# Sheet1.net
KiCad netlist of a schematic drawn in Altium Designer
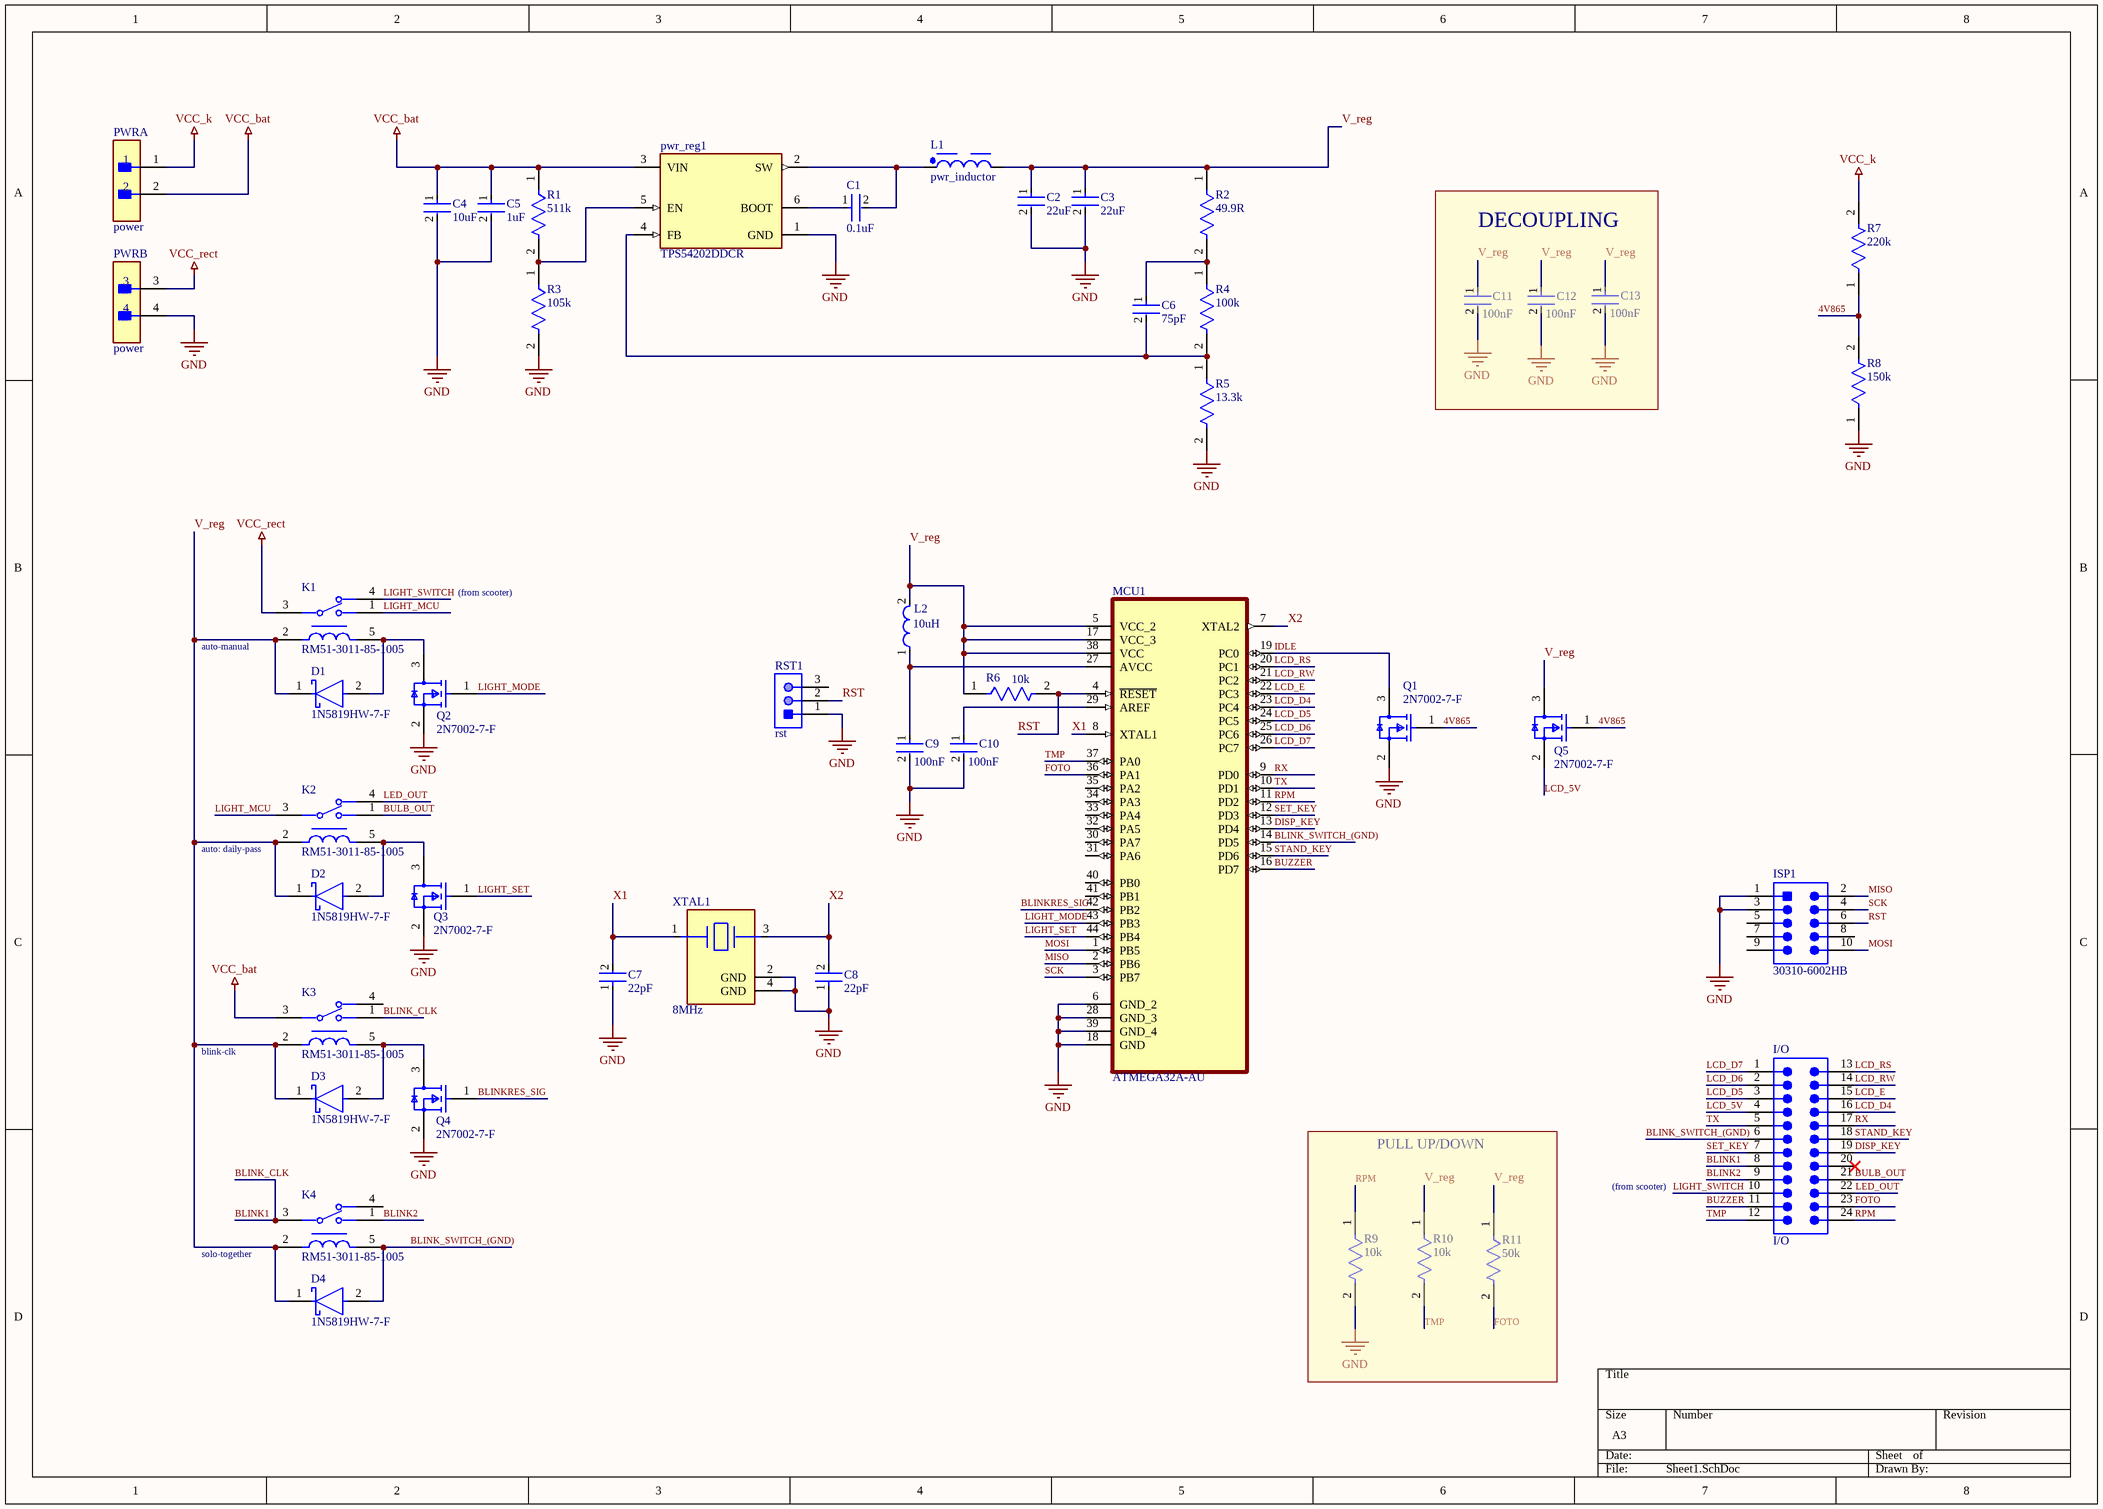
[diagram p0: Sheet1.SchDoc]

(export (version "E")
  (design (tool "Eeschema 10.0.6"))
  (components
    (comp (ref "C1")
      (value "0.1uF")
      (footprint "FP-CL10-IPC_A")
      (description "Cap Ceramic 0.1uF 25V SMD 0603")
      (fields (field (name "VOLTAGE") "50V") (field (name "TOLERANCE") "10%"))
      (libsource (lib "Altium Content Vault") (part "b4654b650e69147ec39a6b967a45e02"))
    )
    (comp (ref "C2")
      (value "22uF")
      (footprint "FP-CL10-IPC_A")
      (description "Cap Ceramic 22uF 25V X7R LOW ESR SMD 0603")
      (fields (field (name "VOLTAGE") "50V") (field (name "TOLERANCE") "10%"))
      (libsource (lib "Altium Content Vault") (part "b4654b650e69147ec39a6b967a45e02"))
    )
    (comp (ref "C3")
      (value "22uF")
      (footprint "FP-CL10-IPC_A")
      (description "Cap Ceramic 22uF 25V X7R LOW ESR SMD 0603")
      (fields (field (name "VOLTAGE") "50V") (field (name "TOLERANCE") "10%"))
      (libsource (lib "Altium Content Vault") (part "b4654b650e69147ec39a6b967a45e02"))
    )
    (comp (ref "C4")
      (value "10uF")
      (footprint "FP-CL10-IPC_A")
      (description "Cap Ceramic 10uF 25V SMD 0603")
      (fields (field (name "VOLTAGE") "50V") (field (name "TOLERANCE") "10%"))
      (libsource (lib "Altium Content Vault") (part "b4654b650e69147ec39a6b967a45e02"))
    )
    (comp (ref "C5")
      (value "1uF")
      (footprint "FP-CL10-IPC_A")
      (description "Cap Ceramic 1uF 25V SMD 0603")
      (fields (field (name "VOLTAGE") "50V") (field (name "TOLERANCE") "10%"))
      (libsource (lib "Altium Content Vault") (part "b4654b650e69147ec39a6b967a45e02"))
    )
    (comp (ref "C6")
      (value "75pF")
      (footprint "FP-CL10-IPC_A")
      (description "Cap Ceramic 75pF 25V SMD 0603")
      (fields (field (name "VOLTAGE") "50V") (field (name "TOLERANCE") "10%"))
      (libsource (lib "Altium Content Vault") (part "b4654b650e69147ec39a6b967a45e02"))
    )
    (comp (ref "C7")
      (value "22pF")
      (footprint "FP-CL10-IPC_A")
      (description "Cap Ceramic 22pF 25V SMD 0603")
      (fields (field (name "VOLTAGE") "50V") (field (name "TOLERANCE") "10%"))
      (libsource (lib "Altium Content Vault") (part "b4654b650e69147ec39a6b967a45e02"))
    )
    (comp (ref "C8")
      (value "22pF")
      (footprint "FP-CL10-IPC_A")
      (description "Cap Ceramic 22pF 25V SMD 0603")
      (fields (field (name "VOLTAGE") "50V") (field (name "TOLERANCE") "10%"))
      (libsource (lib "Altium Content Vault") (part "b4654b650e69147ec39a6b967a45e02"))
    )
    (comp (ref "C9")
      (value "100nF")
      (footprint "FP-CL10-IPC_A")
      (description "Cap Ceramic 100nF 50V X7R ±10% Pad SMD 0603 +125°C T/R")
      (fields (field (name "VOLTAGE") "50V") (field (name "TOLERANCE") "10%"))
      (libsource (lib "Altium Content Vault") (part "b4654b650e69147ec39a6b967a45e02"))
    )
    (comp (ref "C10")
      (value "100nF")
      (footprint "FP-CL10-IPC_A")
      (description "Cap Ceramic 100nF 50V X7R ±10% Pad SMD 0603 +125°C T/R")
      (fields (field (name "VOLTAGE") "50V") (field (name "TOLERANCE") "10%"))
      (libsource (lib "Altium Content Vault") (part "b4654b650e69147ec39a6b967a45e02"))
    )
    (comp (ref "C11")
      (value "100nF")
      (footprint "FP-CL10-IPC_A")
      (description "Cap Ceramic 100nF 50V X7R ±10% Pad SMD 0603 +125°C T/R")
      (fields (field (name "VOLTAGE") "50V") (field (name "TOLERANCE") "10%"))
      (libsource (lib "Altium Content Vault") (part "b4654b650e69147ec39a6b967a45e02"))
    )
    (comp (ref "C12")
      (value "100nF")
      (footprint "FP-CL10-IPC_A")
      (description "Cap Ceramic 100nF 50V X7R ±10% Pad SMD 0603 +125°C T/R")
      (fields (field (name "VOLTAGE") "50V") (field (name "TOLERANCE") "10%"))
      (libsource (lib "Altium Content Vault") (part "b4654b650e69147ec39a6b967a45e02"))
    )
    (comp (ref "C13")
      (value "100nF")
      (footprint "FP-CL10-IPC_A")
      (description "Cap Ceramic 100nF 50V X7R ±10% Pad SMD 0603 +125°C T/R")
      (fields (field (name "VOLTAGE") "50V") (field (name "TOLERANCE") "10%"))
      (libsource (lib "Altium Content Vault") (part "b4654b650e69147ec39a6b967a45e02"))
    )
    (comp (ref "D1")
      (value "1N5819HW-7-F")
      (footprint "FP-SOD123-IPC_A")
      (description "DIODE SCHOTTKY 40V 1A SOD123")
      (libsource (lib "Altium Content Vault") (part "1d6ec82d83fb6aee721767c19dac4b9"))
    )
    (comp (ref "D2")
      (value "1N5819HW-7-F")
      (footprint "FP-SOD123-IPC_A")
      (description "DIODE SCHOTTKY 40V 1A SOD123")
      (libsource (lib "Altium Content Vault") (part "1d6ec82d83fb6aee721767c19dac4b9"))
    )
    (comp (ref "D3")
      (value "1N5819HW-7-F")
      (footprint "FP-SOD123-IPC_A")
      (description "DIODE SCHOTTKY 40V 1A SOD123")
      (libsource (lib "Altium Content Vault") (part "1d6ec82d83fb6aee721767c19dac4b9"))
    )
    (comp (ref "D4")
      (value "1N5819HW-7-F")
      (footprint "FP-SOD123-IPC_A")
      (description "DIODE SCHOTTKY 40V 1A SOD123")
      (libsource (lib "Altium Content Vault") (part "1d6ec82d83fb6aee721767c19dac4b9"))
    )
    (comp (ref "I/O")
      (value "I/O")
      (footprint "649024227222")
      (libsource (lib "Altium Content Vault") (part "Header_Male_2R_24P(A)"))
    )
    (comp (ref "ISP1")
      (value "30310-6002HB")
      (footprint "3M-30310-6002HB-10_V")
      (fields (field (name "MANUFACTURER") "3M"))
      (libsource (lib "Altium Content Vault") (part "CN-2P-M-R10"))
    )
    (comp (ref "K1")
      (value "RM51-3011-85-1005")
      (footprint "FP-1-1721150-0-MFG")
      (description "Relpol\r\nRM51-3011-85-1005\r\nRELAY 10A 5V")
      (fields
        (field (name "MANUFACTURER") "TE")
        (field (name "OCTOPART") "https://octopart.com/1-1721150-0-te+connectivity-41294869")
      )
      (libsource (lib "Altium Content Vault") (part "6d7f6cec76f9d90da65a396cf24d809"))
    )
    (comp (ref "K2")
      (value "RM51-3011-85-1005")
      (footprint "FP-1-1721150-0-MFG")
      (description "Relpol\r\nRM51-3011-85-1005\r\nRELAY 10A 5V")
      (fields
        (field (name "MANUFACTURER") "TE")
        (field (name "OCTOPART") "https://octopart.com/1-1721150-0-te+connectivity-41294869")
      )
      (libsource (lib "Altium Content Vault") (part "6d7f6cec76f9d90da65a396cf24d809"))
    )
    (comp (ref "K3")
      (value "RM51-3011-85-1005")
      (footprint "FP-1-1721150-0-MFG")
      (description "Relpol\r\nRM51-3011-85-1005\r\nRELAY 10A 5V")
      (fields
        (field (name "MANUFACTURER") "TE")
        (field (name "OCTOPART") "https://octopart.com/1-1721150-0-te+connectivity-41294869")
      )
      (libsource (lib "Altium Content Vault") (part "6d7f6cec76f9d90da65a396cf24d809"))
    )
    (comp (ref "K4")
      (value "RM51-3011-85-1005")
      (footprint "FP-1-1721150-0-MFG")
      (description "Relpol\r\nRM51-3011-85-1005\r\nRELAY 10A 5V")
      (fields
        (field (name "MANUFACTURER") "TE")
        (field (name "OCTOPART") "https://octopart.com/1-1721150-0-te+connectivity-41294869")
      )
      (libsource (lib "Altium Content Vault") (part "6d7f6cec76f9d90da65a396cf24d809"))
    )
    (comp (ref "L1")
      (value "pwr_inductor")
      (footprint "WE-PD_7345")
      (description "15uF, 2.7A  HPI0630-150")
      (fields (field (name "TOLERANCE") "20%"))
      (libsource (lib "Altium Content Vault") (part "Inductor - 2"))
    )
    (comp (ref "L2")
      (value "10uH")
      (footprint "FP-CBMF1608-IPC_A")
      (description "SMD Inductors 10uH ±10% 0.38A 0.468Ω 0603")
      (fields (field (name "TOLERANCE") "10%"))
      (libsource (lib "Altium Content Vault") (part "725321dda6339637d4d059423bc1c3c"))
    )
    (comp (ref "MCU1")
      (value "ATMEGA32A-AU")
      (footprint "QFP80P1200X1200X120-44N")
      (description "AVR AVRÂ® ATmega Microcontroller IC 8-Bit 16MHz 32KB (16K x 16) FLASH 44-TQFP (10x10)")
      (fields (field (name "MF") "Microchip"))
      (libsource (lib "ATMEGA32A-AU") (part "ATMEGA32A-AU"))
    )
    (comp (ref "PWR")
      (value "power")
      (footprint "FP-1586042-4-MFG")
      (description "CONN HEADER R/A 4POS 4.2MM")
      (libsource (lib "Altium Content Vault") (part "54be066d535c0aa4221644b3767ed93"))
    )
    (comp (ref "pwr_reg1")
      (value "TPS54202DDCR")
      (footprint "FP-DDC0006A-IPC_B")
      (description "IC REG BUCK ADJ 2A TSOT23-6")
      (libsource (lib "Altium Content Vault") (part "35c2d3f1afc239a386b2ba50eead654"))
    )
    (comp (ref "Q1")
      (value "2N7002-7-F")
      (footprint "FP-SOT23-MFG")
      (description "MOSFET N-CH 60V 115MA SOT23-3")
      (fields (field (name "VOLTAGE") "60V"))
      (libsource (lib "Altium Content Vault") (part "3b9c635fedb024a5347a57b145af9cc"))
    )
    (comp (ref "Q2")
      (value "2N7002-7-F")
      (footprint "FP-SOT23-MFG")
      (description "MOSFET N-CH 60V 115MA SOT23-3")
      (fields (field (name "VOLTAGE") "60V"))
      (libsource (lib "Altium Content Vault") (part "3b9c635fedb024a5347a57b145af9cc"))
    )
    (comp (ref "Q3")
      (value "2N7002-7-F")
      (footprint "FP-SOT23-MFG")
      (description "MOSFET N-CH 60V 115MA SOT23-3")
      (fields (field (name "VOLTAGE") "60V"))
      (libsource (lib "Altium Content Vault") (part "3b9c635fedb024a5347a57b145af9cc"))
    )
    (comp (ref "Q4")
      (value "2N7002-7-F")
      (footprint "FP-SOT23-MFG")
      (description "MOSFET N-CH 60V 115MA SOT23-3")
      (fields (field (name "VOLTAGE") "60V"))
      (libsource (lib "Altium Content Vault") (part "3b9c635fedb024a5347a57b145af9cc"))
    )
    (comp (ref "Q5")
      (value "2N7002-7-F")
      (footprint "FP-SOT23-MFG")
      (description "MOSFET N-CH 60V 115MA SOT23-3")
      (fields (field (name "VOLTAGE") "60V"))
      (libsource (lib "Altium Content Vault") (part "3b9c635fedb024a5347a57b145af9cc"))
    )
    (comp (ref "R1")
      (value "511k")
      (footprint "FP-CRCW0603-e3-IPC_A")
      (description "511kΩ, 0.1W, 0603")
      (fields (field (name "TOLERANCE") "1%"))
      (libsource (lib "Altium Content Vault") (part "1029c3af85768c4190bb7ad29bc67b5"))
    )
    (comp (ref "R2")
      (value "49.9R")
      (footprint "FP-CRCW0603-e3-IPC_A")
      (description "49.9Ω, 0.1W, 0603")
      (fields (field (name "TOLERANCE") "1%"))
      (libsource (lib "Altium Content Vault") (part "1029c3af85768c4190bb7ad29bc67b5"))
    )
    (comp (ref "R3")
      (value "105k")
      (footprint "FP-CRCW0603-e3-IPC_A")
      (description "105kΩ, 0.1W, 0603")
      (fields (field (name "TOLERANCE") "1%"))
      (libsource (lib "Altium Content Vault") (part "1029c3af85768c4190bb7ad29bc67b5"))
    )
    (comp (ref "R4")
      (value "100k")
      (footprint "FP-CRCW0603-e3-IPC_A")
      (description "100kΩ, 0.1W, 0603")
      (fields (field (name "TOLERANCE") "1%"))
      (libsource (lib "Altium Content Vault") (part "1029c3af85768c4190bb7ad29bc67b5"))
    )
    (comp (ref "R5")
      (value "13.3k")
      (footprint "FP-CRCW0603-e3-IPC_A")
      (description "13.3kΩ, 0.1W, 0603")
      (fields (field (name "TOLERANCE") "1%"))
      (libsource (lib "Altium Content Vault") (part "1029c3af85768c4190bb7ad29bc67b5"))
    )
    (comp (ref "R6")
      (value "10k")
      (footprint "FP-CRCW0603-e3-IPC_A")
      (description "10kΩ, 0.1W, 0603")
      (fields (field (name "TOLERANCE") "1%"))
      (libsource (lib "Altium Content Vault") (part "1029c3af85768c4190bb7ad29bc67b5"))
    )
    (comp (ref "R7")
      (value "220k")
      (footprint "FP-CRCW0603-e3-IPC_A")
      (description "220kΩ, 0.1W, 0603")
      (fields (field (name "TOLERANCE") "1%"))
      (libsource (lib "Altium Content Vault") (part "1029c3af85768c4190bb7ad29bc67b5"))
    )
    (comp (ref "R8")
      (value "150k")
      (footprint "FP-CRCW0603-e3-IPC_A")
      (description "150kΩ, 0.1W, 0603")
      (fields (field (name "TOLERANCE") "1%"))
      (libsource (lib "Altium Content Vault") (part "1029c3af85768c4190bb7ad29bc67b5"))
    )
    (comp (ref "R9")
      (value "10k")
      (footprint "FP-CRCW0603-e3-IPC_A")
      (description "10kΩ, 0.1W, 0603")
      (fields (field (name "TOLERANCE") "1%"))
      (libsource (lib "Altium Content Vault") (part "1029c3af85768c4190bb7ad29bc67b5"))
    )
    (comp (ref "R10")
      (value "10k")
      (footprint "FP-CRCW0603-e3-IPC_A")
      (description "10kΩ, 0.1W, 0603")
      (fields (field (name "TOLERANCE") "1%"))
      (libsource (lib "Altium Content Vault") (part "1029c3af85768c4190bb7ad29bc67b5"))
    )
    (comp (ref "R11")
      (value "50k")
      (footprint "FP-CRCW0603-e3-IPC_A")
      (description "50kΩ, 0.1W, 0603")
      (fields (field (name "TOLERANCE") "1%"))
      (libsource (lib "Altium Content Vault") (part "1029c3af85768c4190bb7ad29bc67b5"))
    )
    (comp (ref "RST1")
      (value "rst")
      (footprint "MOLX-22-28-4033_V")
      (description "Male Header, Pitch 2.54 mm, 1 x 3 Position, Height 8.38 mm, Tail Length 3.18 mm, RoHS, Bulk")
      (fields (field (name "MANUFACTURER") "Molex"))
      (libsource (lib "Altium Content Vault") (part "CN-1P-M-R3"))
    )
    (comp (ref "XTAL1")
      (value "8MHz")
      (footprint "FP-LFXTAL055663REEL-MFG")
      (description "LFXTAL055663REEL\r\nCRYSTAL 8.0000MHZ 18PF SMD")
      (libsource (lib "Altium Content Vault") (part "b89083c918a6a788f8f4b4140568890"))
    )
  )
  (nets
    (net (code "1") (name "/4V865") (class "Default")
      (node (ref "Q1") (pin "1") (pinfunction "G_1") (pintype "passive"))
      (node (ref "Q5") (pin "1") (pinfunction "G_1") (pintype "passive"))
      (node (ref "R7") (pin "1") (pinfunction "1_1") (pintype "passive"))
      (node (ref "R8") (pin "2") (pinfunction "2_2") (pintype "passive"))
    )
    (net (code "3") (name "/BLINK1") (class "Default")
      (node (ref "I/O") (pin "8") (pinfunction "8_8") (pintype "passive"))
      (node (ref "K3") (pin "1") (pinfunction "1_1") (pintype "passive"))
      (node (ref "K4") (pin "3") (pinfunction "3_3") (pintype "passive"))
    )
    (net (code "4") (name "/BLINK2") (class "Default")
      (node (ref "I/O") (pin "9") (pinfunction "9_9") (pintype "passive"))
      (node (ref "K4") (pin "1") (pinfunction "1_1") (pintype "passive"))
    )
    (net (code "5") (name "/BLINKRES_SIG") (class "Default")
      (node (ref "MCU1") (pin "42") (pinfunction "PB2_42") (pintype "bidirectional"))
      (node (ref "Q4") (pin "1") (pinfunction "G_1") (pintype "passive"))
    )
    (net (code "6") (name "/BLINK_SWITCH_(GND)") (class "Default")
      (node (ref "D4") (pin "2") (pinfunction "A_2") (pintype "passive"))
      (node (ref "I/O") (pin "6") (pinfunction "6_6") (pintype "passive"))
      (node (ref "K4") (pin "5") (pinfunction "5_5") (pintype "passive"))
      (node (ref "MCU1") (pin "14") (pinfunction "PD5_14") (pintype "bidirectional"))
    )
    (net (code "7") (name "/BULB_OUT") (class "Default")
      (node (ref "I/O") (pin "21") (pinfunction "21_21") (pintype "passive"))
      (node (ref "K2") (pin "1") (pinfunction "1_1") (pintype "passive"))
    )
    (net (code "8") (name "/BUZZER") (class "Default")
      (node (ref "I/O") (pin "11") (pinfunction "11_11") (pintype "passive"))
      (node (ref "MCU1") (pin "16") (pinfunction "PD7_16") (pintype "bidirectional"))
    )
    (net (code "9") (name "/DISP_KEY") (class "Default")
      (node (ref "I/O") (pin "19") (pinfunction "19_19") (pintype "passive"))
      (node (ref "MCU1") (pin "13") (pinfunction "PD4_13") (pintype "bidirectional"))
    )
    (net (code "10") (name "/FOTO") (class "Default")
      (node (ref "I/O") (pin "23") (pinfunction "23_23") (pintype "passive"))
      (node (ref "MCU1") (pin "36") (pinfunction "PA1_36") (pintype "bidirectional"))
      (node (ref "R11") (pin "2") (pinfunction "2_2") (pintype "passive"))
    )
    (net (code "11") (name "/IDLE") (class "Default")
      (node (ref "MCU1") (pin "19") (pinfunction "PC0_19") (pintype "bidirectional"))
      (node (ref "Q1") (pin "3") (pinfunction "D_3") (pintype "passive"))
    )
    (net (code "12") (name "/LCD_5V") (class "Default")
      (node (ref "I/O") (pin "4") (pinfunction "4_4") (pintype "passive"))
      (node (ref "Q5") (pin "2") (pinfunction "S_2") (pintype "passive"))
    )
    (net (code "13") (name "/LCD_D4") (class "Default")
      (node (ref "I/O") (pin "16") (pinfunction "16_16") (pintype "passive"))
      (node (ref "MCU1") (pin "23") (pinfunction "PC4_23") (pintype "bidirectional"))
    )
    (net (code "14") (name "/LCD_D5") (class "Default")
      (node (ref "I/O") (pin "3") (pinfunction "3_3") (pintype "passive"))
      (node (ref "MCU1") (pin "24") (pinfunction "PC5_24") (pintype "bidirectional"))
    )
    (net (code "15") (name "/LCD_D6") (class "Default")
      (node (ref "I/O") (pin "2") (pinfunction "2_2") (pintype "passive"))
      (node (ref "MCU1") (pin "25") (pinfunction "PC6_25") (pintype "bidirectional"))
    )
    (net (code "16") (name "/LCD_D7") (class "Default")
      (node (ref "I/O") (pin "1") (pinfunction "1_1") (pintype "passive"))
      (node (ref "MCU1") (pin "26") (pinfunction "PC7_26") (pintype "bidirectional"))
    )
    (net (code "17") (name "/LCD_E") (class "Default")
      (node (ref "I/O") (pin "15") (pinfunction "15_15") (pintype "passive"))
      (node (ref "MCU1") (pin "22") (pinfunction "PC3_22") (pintype "bidirectional"))
    )
    (net (code "18") (name "/LCD_RS") (class "Default")
      (node (ref "I/O") (pin "13") (pinfunction "13_13") (pintype "passive"))
      (node (ref "MCU1") (pin "20") (pinfunction "PC1_20") (pintype "bidirectional"))
    )
    (net (code "19") (name "/LCD_RW") (class "Default")
      (node (ref "I/O") (pin "14") (pinfunction "14_14") (pintype "passive"))
      (node (ref "MCU1") (pin "21") (pinfunction "PC2_21") (pintype "bidirectional"))
    )
    (net (code "20") (name "/LED_OUT") (class "Default")
      (node (ref "I/O") (pin "22") (pinfunction "22_22") (pintype "passive"))
      (node (ref "K2") (pin "4") (pinfunction "4_4") (pintype "passive"))
    )
    (net (code "21") (name "/LIGHT_MCU") (class "Default")
      (node (ref "K1") (pin "1") (pinfunction "1_1") (pintype "passive"))
      (node (ref "K2") (pin "3") (pinfunction "3_3") (pintype "passive"))
    )
    (net (code "22") (name "/LIGHT_MODE") (class "Default")
      (node (ref "MCU1") (pin "43") (pinfunction "PB3_43") (pintype "bidirectional"))
      (node (ref "Q2") (pin "1") (pinfunction "G_1") (pintype "passive"))
    )
    (net (code "23") (name "/LIGHT_SET") (class "Default")
      (node (ref "MCU1") (pin "44") (pinfunction "PB4_44") (pintype "bidirectional"))
      (node (ref "Q3") (pin "1") (pinfunction "G_1") (pintype "passive"))
    )
    (net (code "24") (name "/LIGHT_SWITCH") (class "Default")
      (node (ref "I/O") (pin "10") (pinfunction "10_10") (pintype "passive"))
      (node (ref "K1") (pin "4") (pinfunction "4_4") (pintype "passive"))
    )
    (net (code "25") (name "/MISO") (class "Default")
      (node (ref "ISP1") (pin "2") (pinfunction "2_2") (pintype "passive"))
      (node (ref "MCU1") (pin "2") (pinfunction "PB6_2") (pintype "bidirectional"))
    )
    (net (code "26") (name "/MOSI") (class "Default")
      (node (ref "ISP1") (pin "10") (pinfunction "10_10") (pintype "passive"))
      (node (ref "MCU1") (pin "1") (pinfunction "PB5_1") (pintype "bidirectional"))
    )
    (net (code "27") (name "/RPM") (class "Default")
      (node (ref "I/O") (pin "24") (pinfunction "24_24") (pintype "passive"))
      (node (ref "MCU1") (pin "11") (pinfunction "PD2_11") (pintype "bidirectional"))
      (node (ref "R9") (pin "1") (pinfunction "1_1") (pintype "passive"))
    )
    (net (code "28") (name "/RST") (class "Default")
      (node (ref "ISP1") (pin "6") (pinfunction "6_6") (pintype "passive"))
      (node (ref "MCU1") (pin "4") (pinfunction "~{RESET}_4") (pintype "input"))
      (node (ref "R6") (pin "2") (pinfunction "2_2") (pintype "passive"))
      (node (ref "RST1") (pin "2") (pinfunction "2_2") (pintype "passive"))
    )
    (net (code "29") (name "/RX") (class "Default")
      (node (ref "I/O") (pin "17") (pinfunction "17_17") (pintype "passive"))
      (node (ref "MCU1") (pin "9") (pinfunction "PD0_9") (pintype "bidirectional"))
    )
    (net (code "30") (name "/SCK") (class "Default")
      (node (ref "ISP1") (pin "4") (pinfunction "4_4") (pintype "passive"))
      (node (ref "MCU1") (pin "3") (pinfunction "PB7_3") (pintype "bidirectional"))
    )
    (net (code "31") (name "/SET_KEY") (class "Default")
      (node (ref "I/O") (pin "7") (pinfunction "7_7") (pintype "passive"))
      (node (ref "MCU1") (pin "12") (pinfunction "PD3_12") (pintype "bidirectional"))
    )
    (net (code "32") (name "/STAND_KEY") (class "Default")
      (node (ref "I/O") (pin "18") (pinfunction "18_18") (pintype "passive"))
      (node (ref "MCU1") (pin "15") (pinfunction "PD6_15") (pintype "bidirectional"))
    )
    (net (code "33") (name "/TMP") (class "Default")
      (node (ref "I/O") (pin "12") (pinfunction "12_12") (pintype "passive"))
      (node (ref "MCU1") (pin "37") (pinfunction "PA0_37") (pintype "bidirectional"))
      (node (ref "R10") (pin "2") (pinfunction "2_2") (pintype "passive"))
    )
    (net (code "34") (name "/TX") (class "Default")
      (node (ref "I/O") (pin "5") (pinfunction "5_5") (pintype "passive"))
      (node (ref "MCU1") (pin "10") (pinfunction "PD1_10") (pintype "bidirectional"))
    )
    (net (code "35") (name "/V_reg") (class "Default")
      (node (ref "C11") (pin "1") (pinfunction "1_1") (pintype "passive"))
      (node (ref "C12") (pin "1") (pinfunction "1_1") (pintype "passive"))
      (node (ref "C13") (pin "1") (pinfunction "1_1") (pintype "passive"))
      (node (ref "C2") (pin "1") (pinfunction "1_1") (pintype "passive"))
      (node (ref "C3") (pin "1") (pinfunction "1_1") (pintype "passive"))
      (node (ref "D1") (pin "1") (pinfunction "C_1") (pintype "passive"))
      (node (ref "D2") (pin "1") (pinfunction "C_1") (pintype "passive"))
      (node (ref "D3") (pin "1") (pinfunction "C_1") (pintype "passive"))
      (node (ref "D4") (pin "1") (pinfunction "C_1") (pintype "passive"))
      (node (ref "K1") (pin "2") (pinfunction "2_2") (pintype "passive"))
      (node (ref "K2") (pin "2") (pinfunction "2_2") (pintype "passive"))
      (node (ref "K3") (pin "2") (pinfunction "2_2") (pintype "passive"))
      (node (ref "K4") (pin "2") (pinfunction "2_2") (pintype "passive"))
      (node (ref "L1") (pin "2") (pinfunction "2_2") (pintype "passive"))
      (node (ref "L2") (pin "2") (pinfunction "2_2") (pintype "passive"))
      (node (ref "MCU1") (pin "17") (pinfunction "VCC_3_17") (pintype "power_in"))
      (node (ref "MCU1") (pin "38") (pinfunction "VCC_38") (pintype "power_in"))
      (node (ref "MCU1") (pin "5") (pinfunction "VCC_2_5") (pintype "power_in"))
      (node (ref "Q5") (pin "3") (pinfunction "D_3") (pintype "passive"))
      (node (ref "R10") (pin "1") (pinfunction "1_1") (pintype "passive"))
      (node (ref "R11") (pin "1") (pinfunction "1_1") (pintype "passive"))
      (node (ref "R2") (pin "1") (pinfunction "1_1") (pintype "passive"))
      (node (ref "R6") (pin "1") (pinfunction "1_1") (pintype "passive"))
    )
    (net (code "36") (name "/X1") (class "Default")
      (node (ref "C7") (pin "2") (pinfunction "2_2") (pintype "passive"))
      (node (ref "MCU1") (pin "8") (pinfunction "XTAL1_8") (pintype "input"))
      (node (ref "XTAL1") (pin "1") (pinfunction "1_CRYSTAL_1") (pintype "passive"))
    )
    (net (code "37") (name "/X2") (class "Default")
      (node (ref "C8") (pin "2") (pinfunction "2_2") (pintype "passive"))
      (node (ref "MCU1") (pin "7") (pinfunction "XTAL2_7") (pintype "output"))
      (node (ref "XTAL1") (pin "3") (pinfunction "2_CRYSTAL_3") (pintype "passive"))
    )
    (net (code "38") (name "GND") (class "Default")
      (node (ref "C10") (pin "2") (pinfunction "2_2") (pintype "passive"))
      (node (ref "C11") (pin "2") (pinfunction "2_2") (pintype "passive"))
      (node (ref "C12") (pin "2") (pinfunction "2_2") (pintype "passive"))
      (node (ref "C13") (pin "2") (pinfunction "2_2") (pintype "passive"))
      (node (ref "C2") (pin "2") (pinfunction "2_2") (pintype "passive"))
      (node (ref "C3") (pin "2") (pinfunction "2_2") (pintype "passive"))
      (node (ref "C4") (pin "2") (pinfunction "2_2") (pintype "passive"))
      (node (ref "C5") (pin "2") (pinfunction "2_2") (pintype "passive"))
      (node (ref "C7") (pin "1") (pinfunction "1_1") (pintype "passive"))
      (node (ref "C8") (pin "1") (pinfunction "1_1") (pintype "passive"))
      (node (ref "C9") (pin "2") (pinfunction "2_2") (pintype "passive"))
      (node (ref "ISP1") (pin "1") (pinfunction "1_1") (pintype "passive"))
      (node (ref "ISP1") (pin "3") (pinfunction "3_3") (pintype "passive"))
      (node (ref "MCU1") (pin "18") (pinfunction "GND_18") (pintype "passive"))
      (node (ref "MCU1") (pin "28") (pinfunction "GND_3_28") (pintype "passive"))
      (node (ref "MCU1") (pin "39") (pinfunction "GND_4_39") (pintype "passive"))
      (node (ref "MCU1") (pin "6") (pinfunction "GND_2_6") (pintype "passive"))
      (node (ref "PWR") (pin "4") (pinfunction "4_4") (pintype "passive"))
      (node (ref "Q1") (pin "2") (pinfunction "S_2") (pintype "passive"))
      (node (ref "Q2") (pin "2") (pinfunction "S_2") (pintype "passive"))
      (node (ref "Q3") (pin "2") (pinfunction "S_2") (pintype "passive"))
      (node (ref "Q4") (pin "2") (pinfunction "S_2") (pintype "passive"))
      (node (ref "R3") (pin "2") (pinfunction "2_2") (pintype "passive"))
      (node (ref "R5") (pin "2") (pinfunction "2_2") (pintype "passive"))
      (node (ref "R8") (pin "1") (pinfunction "1_1") (pintype "passive"))
      (node (ref "R9") (pin "2") (pinfunction "2_2") (pintype "passive"))
      (node (ref "RST1") (pin "1") (pinfunction "1_1") (pintype "passive"))
      (node (ref "XTAL1") (pin "2") (pinfunction "GND_2") (pintype "power_in"))
      (node (ref "XTAL1") (pin "4") (pinfunction "GND_4") (pintype "power_in"))
      (node (ref "pwr_reg1") (pin "1") (pinfunction "GND_1") (pintype "power_in"))
    )
    (net (code "39") (name "Net-(C6-Pad1)") (class "Default")
      (node (ref "C6") (pin "1") (pinfunction "1_1") (pintype "passive"))
      (node (ref "R2") (pin "2") (pinfunction "2_2") (pintype "passive"))
      (node (ref "R4") (pin "1") (pinfunction "1_1") (pintype "passive"))
    )
    (net (code "40") (name "Net-(D1-A)") (class "Default")
      (node (ref "D1") (pin "2") (pinfunction "A_2") (pintype "passive"))
      (node (ref "K1") (pin "5") (pinfunction "5_5") (pintype "passive"))
      (node (ref "Q2") (pin "3") (pinfunction "D_3") (pintype "passive"))
    )
    (net (code "41") (name "Net-(D2-A)") (class "Default")
      (node (ref "D2") (pin "2") (pinfunction "A_2") (pintype "passive"))
      (node (ref "K2") (pin "5") (pinfunction "5_5") (pintype "passive"))
      (node (ref "Q3") (pin "3") (pinfunction "D_3") (pintype "passive"))
    )
    (net (code "42") (name "Net-(D3-A)") (class "Default")
      (node (ref "D3") (pin "2") (pinfunction "A_2") (pintype "passive"))
      (node (ref "K3") (pin "5") (pinfunction "5_5") (pintype "passive"))
      (node (ref "Q4") (pin "3") (pinfunction "D_3") (pintype "passive"))
    )
    (net (code "43") (name "Net-(MCU1-AREF)") (class "Default")
      (node (ref "C10") (pin "1") (pinfunction "1_1") (pintype "passive"))
      (node (ref "MCU1") (pin "29") (pinfunction "AREF_29") (pintype "input"))
    )
    (net (code "44") (name "Net-(MCU1-AVCC)") (class "Default")
      (node (ref "C9") (pin "1") (pinfunction "1_1") (pintype "passive"))
      (node (ref "L2") (pin "1") (pinfunction "1_1") (pintype "passive"))
      (node (ref "MCU1") (pin "27") (pinfunction "AVCC_27") (pintype "power_in"))
    )
    (net (code "45") (name "Net-(pwr_reg1-BOOT)") (class "Default")
      (node (ref "C1") (pin "1") (pinfunction "1_1") (pintype "passive"))
      (node (ref "pwr_reg1") (pin "6") (pinfunction "BOOT_6") (pintype "passive"))
    )
    (net (code "46") (name "Net-(pwr_reg1-EN)") (class "Default")
      (node (ref "R1") (pin "2") (pinfunction "2_2") (pintype "passive"))
      (node (ref "R3") (pin "1") (pinfunction "1_1") (pintype "passive"))
      (node (ref "pwr_reg1") (pin "5") (pinfunction "EN_5") (pintype "input"))
    )
    (net (code "47") (name "Net-(pwr_reg1-FB)") (class "Default")
      (node (ref "C6") (pin "2") (pinfunction "2_2") (pintype "passive"))
      (node (ref "R4") (pin "2") (pinfunction "2_2") (pintype "passive"))
      (node (ref "R5") (pin "1") (pinfunction "1_1") (pintype "passive"))
      (node (ref "pwr_reg1") (pin "4") (pinfunction "FB_4") (pintype "input"))
    )
    (net (code "48") (name "Net-(pwr_reg1-SW)") (class "Default")
      (node (ref "C1") (pin "2") (pinfunction "2_2") (pintype "passive"))
      (node (ref "L1") (pin "1") (pinfunction "1_1") (pintype "passive"))
      (node (ref "pwr_reg1") (pin "2") (pinfunction "SW_2") (pintype "output"))
    )
    (net (code "49") (name "VCC_bat") (class "Default")
      (node (ref "C4") (pin "1") (pinfunction "1_1") (pintype "passive"))
      (node (ref "C5") (pin "1") (pinfunction "1_1") (pintype "passive"))
      (node (ref "K3") (pin "3") (pinfunction "3_3") (pintype "passive"))
      (node (ref "PWR") (pin "2") (pinfunction "2_2") (pintype "passive"))
      (node (ref "R1") (pin "1") (pinfunction "1_1") (pintype "passive"))
      (node (ref "pwr_reg1") (pin "3") (pinfunction "VIN_3") (pintype "power_in"))
    )
    (net (code "50") (name "VCC_k") (class "Default")
      (node (ref "PWR") (pin "1") (pinfunction "1_1") (pintype "passive"))
      (node (ref "R7") (pin "2") (pinfunction "2_2") (pintype "passive"))
    )
    (net (code "51") (name "VCC_rect") (class "Default")
      (node (ref "K1") (pin "3") (pinfunction "3_3") (pintype "passive"))
      (node (ref "PWR") (pin "3") (pinfunction "3_3") (pintype "passive"))
    )
    (net (code "52") (name "unconnected-(I/O-Pad20)") (class "Default")
      (node (ref "I/O") (pin "20") (pinfunction "20_20") (pintype "passive+no_connect"))
    )
    (net (code "53") (name "unconnected-(ISP1-Pad5)") (class "Default")
      (node (ref "ISP1") (pin "5") (pinfunction "5_5") (pintype "passive"))
    )
    (net (code "54") (name "unconnected-(ISP1-Pad7)") (class "Default")
      (node (ref "ISP1") (pin "7") (pinfunction "7_7") (pintype "passive"))
    )
    (net (code "55") (name "unconnected-(ISP1-Pad8)") (class "Default")
      (node (ref "ISP1") (pin "8") (pinfunction "8_8") (pintype "passive"))
    )
    (net (code "56") (name "unconnected-(ISP1-Pad9)") (class "Default")
      (node (ref "ISP1") (pin "9") (pinfunction "9_9") (pintype "passive"))
    )
    (net (code "57") (name "unconnected-(K3-Pad4)") (class "Default")
      (node (ref "K3") (pin "4") (pinfunction "4_4") (pintype "passive"))
    )
    (net (code "58") (name "unconnected-(K4-Pad4)") (class "Default")
      (node (ref "K4") (pin "4") (pinfunction "4_4") (pintype "passive"))
    )
    (net (code "59") (name "unconnected-(MCU1-PA2-Pad35)") (class "Default")
      (node (ref "MCU1") (pin "35") (pinfunction "PA2_35") (pintype "bidirectional"))
    )
    (net (code "60") (name "unconnected-(MCU1-PA3-Pad34)") (class "Default")
      (node (ref "MCU1") (pin "34") (pinfunction "PA3_34") (pintype "bidirectional"))
    )
    (net (code "61") (name "unconnected-(MCU1-PA4-Pad33)") (class "Default")
      (node (ref "MCU1") (pin "33") (pinfunction "PA4_33") (pintype "bidirectional"))
    )
    (net (code "62") (name "unconnected-(MCU1-PA5-Pad32)") (class "Default")
      (node (ref "MCU1") (pin "32") (pinfunction "PA5_32") (pintype "bidirectional"))
    )
    (net (code "63") (name "unconnected-(MCU1-PA6-Pad31)") (class "Default")
      (node (ref "MCU1") (pin "31") (pinfunction "PA6_31") (pintype "bidirectional"))
    )
    (net (code "64") (name "unconnected-(MCU1-PA7-Pad30)") (class "Default")
      (node (ref "MCU1") (pin "30") (pinfunction "PA7_30") (pintype "bidirectional"))
    )
    (net (code "65") (name "unconnected-(MCU1-PB0-Pad40)") (class "Default")
      (node (ref "MCU1") (pin "40") (pinfunction "PB0_40") (pintype "bidirectional"))
    )
    (net (code "66") (name "unconnected-(MCU1-PB1-Pad41)") (class "Default")
      (node (ref "MCU1") (pin "41") (pinfunction "PB1_41") (pintype "bidirectional"))
    )
    (net (code "67") (name "unconnected-(RST1-Pad3)") (class "Default")
      (node (ref "RST1") (pin "3") (pinfunction "3_3") (pintype "passive"))
    )
  )
)
